# Temp_Project.net
KiCad netlist of a schematic drawn in EAGLE
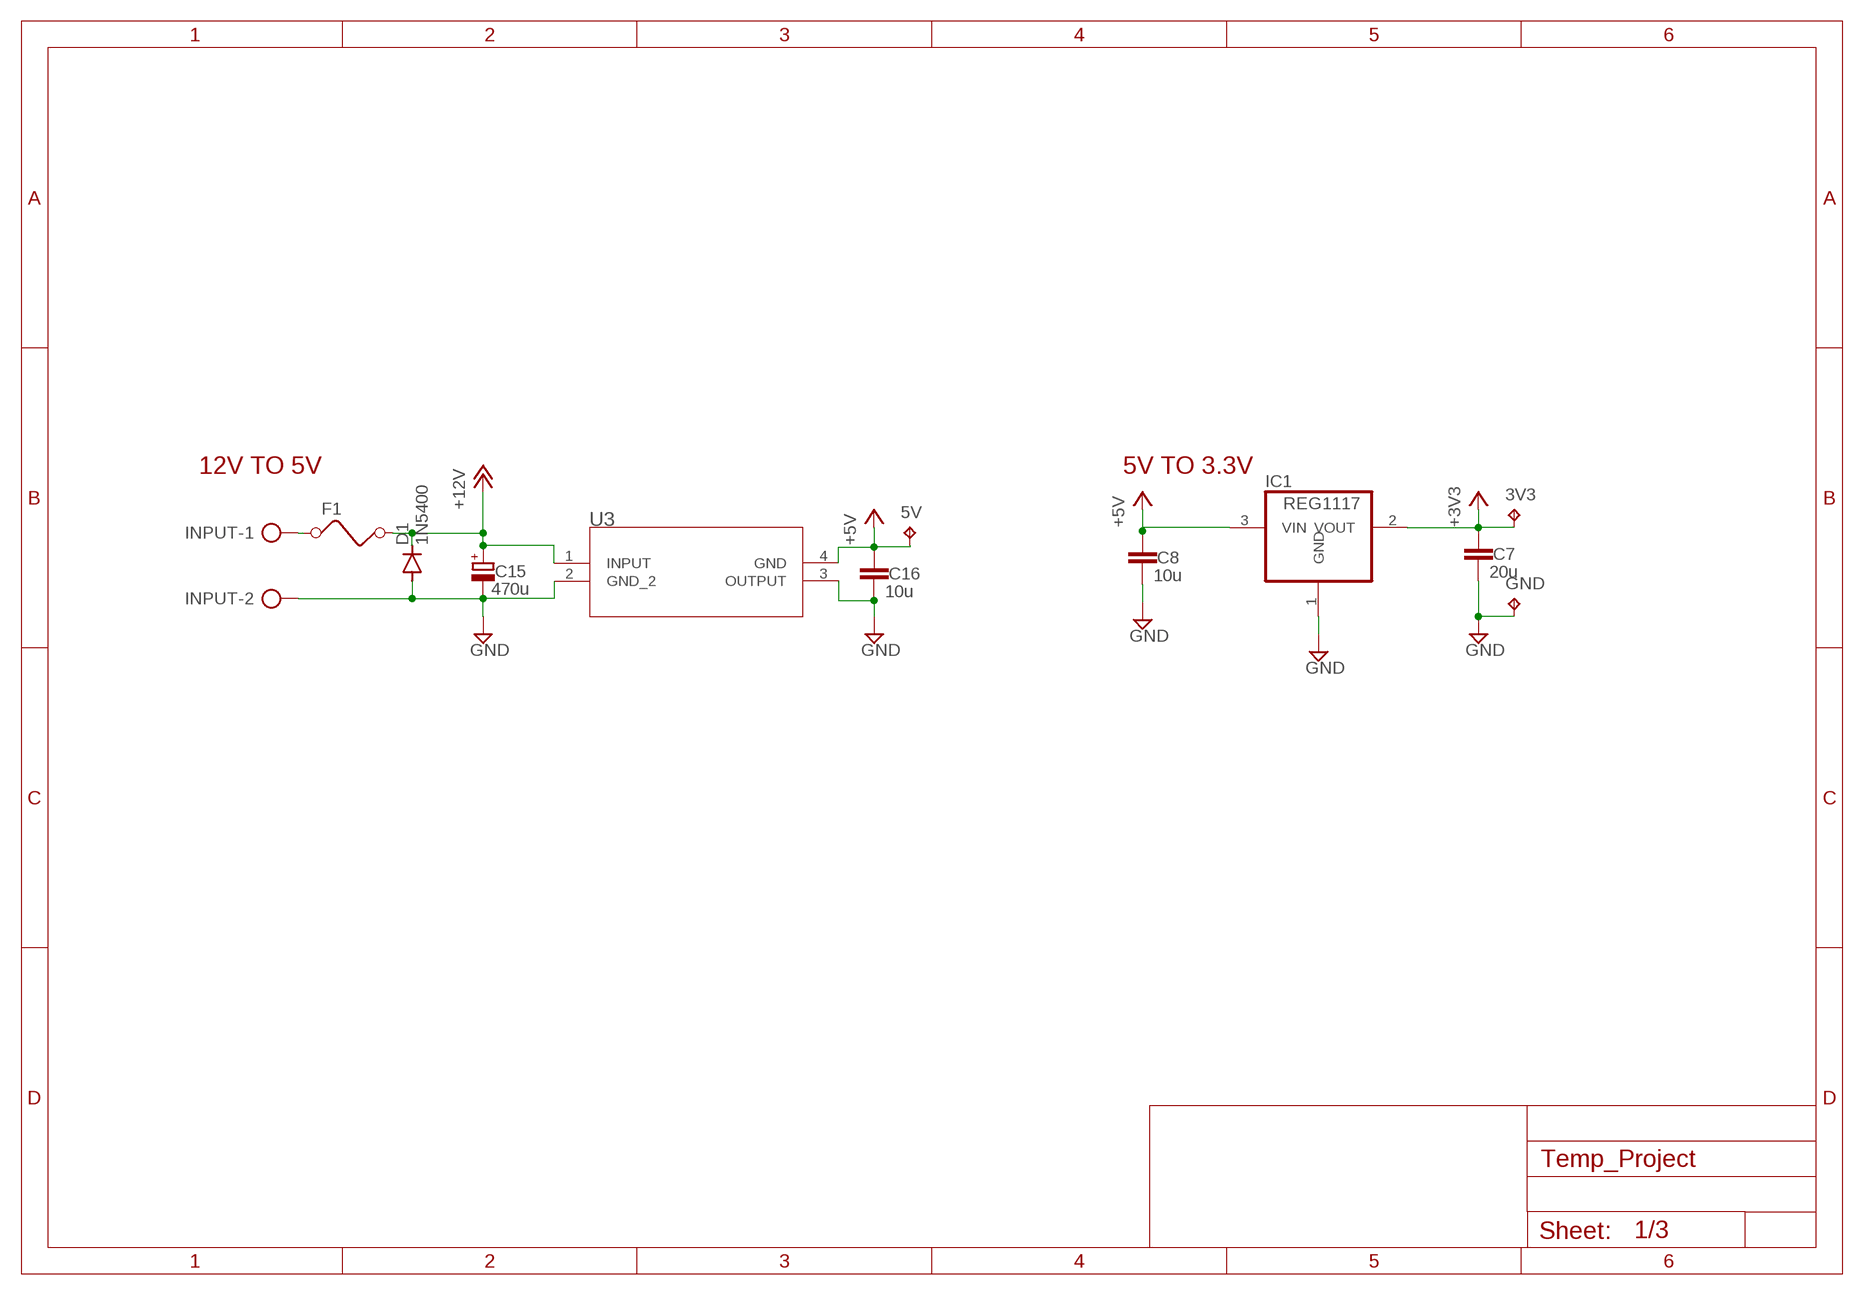
[diagram p0: schematic, sheet 1]
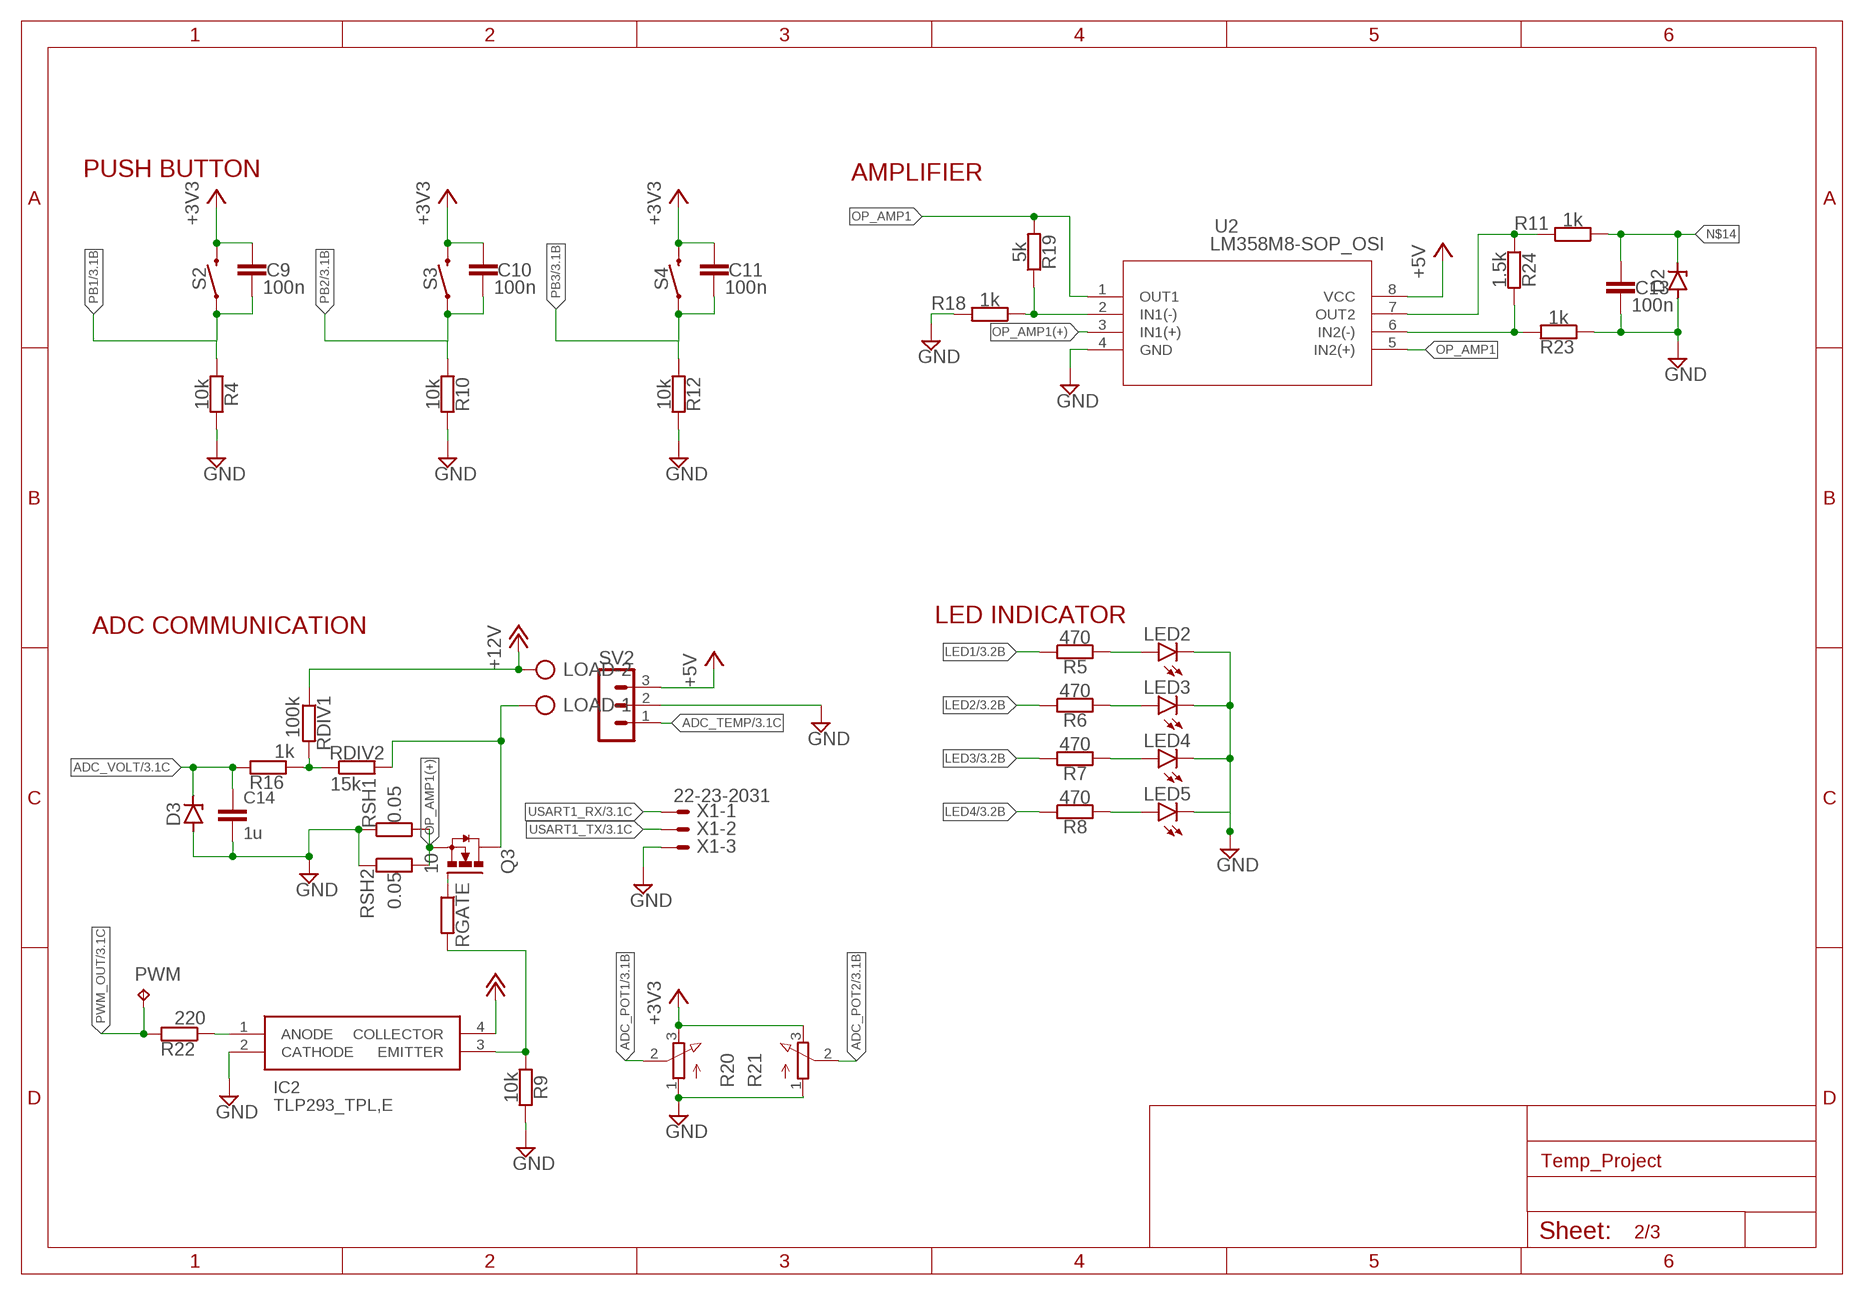
[diagram p1: schematic, sheet 2]
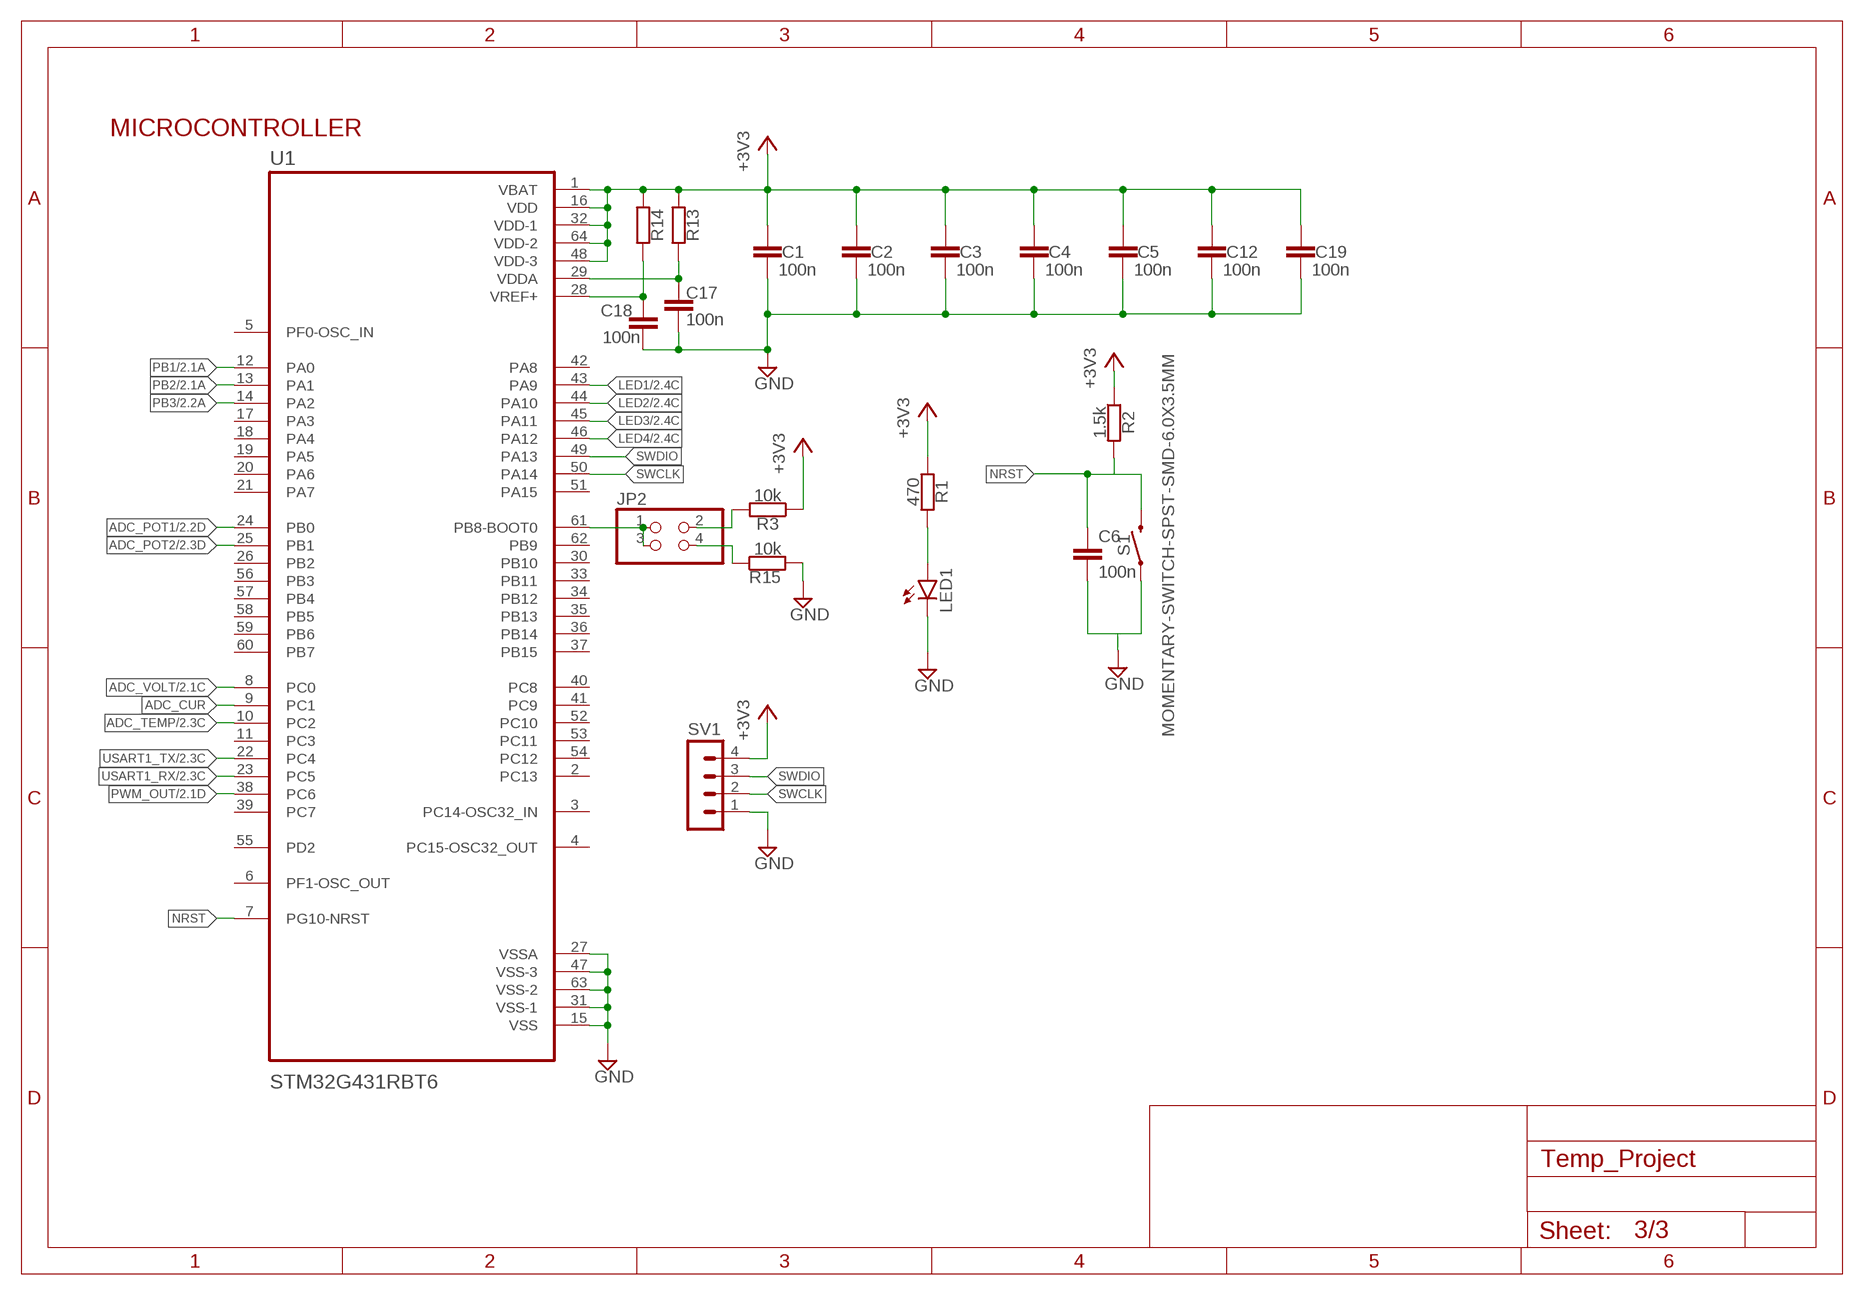
[diagram p2: schematic, sheet 3]

(export (version "E")
  (design (tool "Eeschema 10.0.6"))
  (components
    (comp (ref "C9")
      (value "100n")
      (footprint "eagle-import:C0805")
      (libsource (lib "eagle-import") (part "C-EUC0805"))
    )
    (comp (ref "C10")
      (value "100n")
      (footprint "eagle-import:C0805")
      (libsource (lib "eagle-import") (part "C-EUC0805"))
    )
    (comp (ref "C11")
      (value "100n")
      (footprint "eagle-import:C0805")
      (libsource (lib "eagle-import") (part "C-EUC0805"))
    )
    (comp (ref "C13")
      (value "100n")
      (footprint "eagle-import:C0805")
      (libsource (lib "eagle-import") (part "C-EUC0805"))
    )
    (comp (ref "C14")
      (value "1u")
      (footprint "eagle-import:C0805")
      (libsource (lib "eagle-import") (part "C-EUC0805"))
    )
    (comp (ref "D2")
      (value "ZENER 3V3")
      (footprint "eagle-import:SOD80C")
      (libsource (lib "eagle-import") (part "ZENER-DIODESOD80C"))
    )
    (comp (ref "D3")
      (value "ZENER 3V3")
      (footprint "eagle-import:SOD80C")
      (libsource (lib "eagle-import") (part "ZENER-DIODESOD80C"))
    )
    (comp (ref "IC2")
      (value "TLP293_TPL,E")
      (footprint "eagle-import:SOIC127P700X220-4N")
      (fields
        (field (name "MANUFACTURER_PART_NUMBER") "TLP293(TPL,E")
        (field (name "MOUSER_PART_NUMBER") "757-TLP293TPLE")
      )
      (libsource (lib "eagle-import") (part "TLP293_TPL,E"))
    )
    (comp (ref "LED2")
      (value "LED3MM")
      (footprint "eagle-import:LED3MM")
      (libsource (lib "eagle-import") (part "LED3MM"))
    )
    (comp (ref "LED3")
      (value "LED3MM")
      (footprint "eagle-import:LED3MM")
      (libsource (lib "eagle-import") (part "LED3MM"))
    )
    (comp (ref "LED4")
      (value "LED3MM")
      (footprint "eagle-import:LED3MM")
      (libsource (lib "eagle-import") (part "LED3MM"))
    )
    (comp (ref "LED5")
      (value "LED3MM")
      (footprint "eagle-import:LED3MM")
      (libsource (lib "eagle-import") (part "LED3MM"))
    )
    (comp (ref "LOAD")
      (value "AK500/2-H")
      (footprint "eagle-import:AK500_2-H")
      (libsource (lib "eagle-import") (part "con-ptr500_44290620_AK500/2-H"))
    )
    (comp (ref "PWM")
      (value "TPPAD1-13")
      (footprint "eagle-import:P1-13")
      (libsource (lib "eagle-import") (part "TPPAD1-13"))
    )
    (comp (ref "Q3")
      (value "IRFZ44N")
      (footprint "eagle-import:SOT223")
      (libsource (lib "eagle-import") (part "N-HEXFET-2D_?-SOT232"))
    )
    (comp (ref "R4")
      (value "10k")
      (footprint "eagle-import:R0805")
      (libsource (lib "eagle-import") (part "R-EU_R0805"))
    )
    (comp (ref "R5")
      (value "470")
      (footprint "eagle-import:R0805")
      (libsource (lib "eagle-import") (part "R-EU_R0805"))
    )
    (comp (ref "R6")
      (value "470")
      (footprint "eagle-import:R0805")
      (libsource (lib "eagle-import") (part "R-EU_R0805"))
    )
    (comp (ref "R7")
      (value "470")
      (footprint "eagle-import:R0805")
      (libsource (lib "eagle-import") (part "R-EU_R0805"))
    )
    (comp (ref "R8")
      (value "470")
      (footprint "eagle-import:R0805")
      (libsource (lib "eagle-import") (part "R-EU_R0805"))
    )
    (comp (ref "R9")
      (value "10k")
      (footprint "eagle-import:R0805")
      (libsource (lib "eagle-import") (part "R-EU_R0805"))
    )
    (comp (ref "R10")
      (value "10k")
      (footprint "eagle-import:R0805")
      (libsource (lib "eagle-import") (part "R-EU_R0805"))
    )
    (comp (ref "R11")
      (value "1k")
      (footprint "eagle-import:R0805")
      (libsource (lib "eagle-import") (part "R-EU_R0805"))
    )
    (comp (ref "R12")
      (value "10k")
      (footprint "eagle-import:R0805")
      (libsource (lib "eagle-import") (part "R-EU_R0805"))
    )
    (comp (ref "R16")
      (value "1k")
      (footprint "eagle-import:R0805")
      (libsource (lib "eagle-import") (part "R-EU_R0805"))
    )
    (comp (ref "R18")
      (value "1k")
      (footprint "eagle-import:R0805")
      (libsource (lib "eagle-import") (part "R-EU_R0805"))
    )
    (comp (ref "R19")
      (value "5k")
      (footprint "eagle-import:R0805")
      (libsource (lib "eagle-import") (part "R-EU_R0805"))
    )
    (comp (ref "R20")
      (value "3RP/1610N")
      (footprint "eagle-import:3RP_1610N")
      (libsource (lib "eagle-import") (part "3RP/1610N"))
    )
    (comp (ref "R21")
      (value "3RP/1610N")
      (footprint "eagle-import:3RP_1610N")
      (libsource (lib "eagle-import") (part "3RP/1610N"))
    )
    (comp (ref "R22")
      (value "220")
      (footprint "eagle-import:R0805")
      (libsource (lib "eagle-import") (part "R-EU_R0805"))
    )
    (comp (ref "R23")
      (value "1k")
      (footprint "eagle-import:R0805")
      (libsource (lib "eagle-import") (part "R-EU_R0805"))
    )
    (comp (ref "R24")
      (value "1.5k")
      (footprint "eagle-import:R0805")
      (libsource (lib "eagle-import") (part "R-EU_R0805"))
    )
    (comp (ref "RDIV1")
      (value "100k")
      (footprint "eagle-import:R0805")
      (libsource (lib "eagle-import") (part "R-EU_R0805"))
    )
    (comp (ref "RDIV2")
      (value "15k")
      (footprint "eagle-import:R0805")
      (libsource (lib "eagle-import") (part "R-EU_R0805"))
    )
    (comp (ref "RGATE")
      (value "10")
      (footprint "eagle-import:R0805")
      (libsource (lib "eagle-import") (part "R-EU_R0805"))
    )
    (comp (ref "RSH1")
      (value "0.05")
      (footprint "eagle-import:0617_22")
      (libsource (lib "eagle-import") (part "R-EU_0617/22"))
    )
    (comp (ref "RSH2")
      (value "0.05")
      (footprint "eagle-import:0617_22")
      (libsource (lib "eagle-import") (part "R-EU_0617/22"))
    )
    (comp (ref "S2")
      (value "MOMENTARY-SWITCH-SPST-SMD-6.0X3.5MM")
      (footprint "eagle-import:TACTILE_SWITCH_SMD_6.0X3.5MM")
      (libsource (lib "eagle-import") (part "MOMENTARY-SWITCH-SPST-SMD-6.0X3.5MM"))
    )
    (comp (ref "S3")
      (value "MOMENTARY-SWITCH-SPST-SMD-6.0X3.5MM")
      (footprint "eagle-import:TACTILE_SWITCH_SMD_6.0X3.5MM")
      (libsource (lib "eagle-import") (part "MOMENTARY-SWITCH-SPST-SMD-6.0X3.5MM"))
    )
    (comp (ref "S4")
      (value "MOMENTARY-SWITCH-SPST-SMD-6.0X3.5MM")
      (footprint "eagle-import:TACTILE_SWITCH_SMD_6.0X3.5MM")
      (libsource (lib "eagle-import") (part "MOMENTARY-SWITCH-SPST-SMD-6.0X3.5MM"))
    )
    (comp (ref "SV2")
      (value "MA03-1")
      (footprint "eagle-import:MA03-1")
      (libsource (lib "eagle-import") (part "MA03-1"))
    )
    (comp (ref "U2")
      (value "LM358M8-SOP_OSI")
      (footprint "eagle-import:8-SOP_OSI")
      (fields
        (field (name "MANUFACTURER_PART_NUMBER") "LM358M")
        (field (name "COPYRIGHT") "Copyright (C) 2024 Ultra Librarian. All rights reserved.")
      )
      (libsource (lib "eagle-import") (part "LM358M8-SOP_OSI"))
    )
    (comp (ref "X1")
      (value "22-23-2031")
      (footprint "eagle-import:22-23-2031")
      (fields (field (name "MF") "MOLEX"))
      (libsource (lib "eagle-import") (part "22-23-2031"))
    )
    (comp (ref "C1")
      (value "100n")
      (footprint "eagle-import:C0805")
      (libsource (lib "eagle-import") (part "C-EUC0805"))
    )
    (comp (ref "C2")
      (value "100n")
      (footprint "eagle-import:C0805")
      (libsource (lib "eagle-import") (part "C-EUC0805"))
    )
    (comp (ref "C3")
      (value "100n")
      (footprint "eagle-import:C0805")
      (libsource (lib "eagle-import") (part "C-EUC0805"))
    )
    (comp (ref "C4")
      (value "100n")
      (footprint "eagle-import:C0805")
      (libsource (lib "eagle-import") (part "C-EUC0805"))
    )
    (comp (ref "C5")
      (value "100n")
      (footprint "eagle-import:C0805")
      (libsource (lib "eagle-import") (part "C-EUC0805"))
    )
    (comp (ref "C6")
      (value "100n")
      (footprint "eagle-import:C0805")
      (libsource (lib "eagle-import") (part "C-EUC0805"))
    )
    (comp (ref "C12")
      (value "100n")
      (footprint "eagle-import:C0805")
      (libsource (lib "eagle-import") (part "C-EUC0805"))
    )
    (comp (ref "C17")
      (value "100n")
      (footprint "eagle-import:C0805")
      (libsource (lib "eagle-import") (part "C-EUC0805"))
    )
    (comp (ref "C18")
      (value "100n")
      (footprint "eagle-import:C0805")
      (libsource (lib "eagle-import") (part "C-EUC0805"))
    )
    (comp (ref "C19")
      (value "100n")
      (footprint "eagle-import:C0805")
      (libsource (lib "eagle-import") (part "C-EUC0805"))
    )
    (comp (ref "JP2")
      (value "PINHD-2X2")
      (footprint "eagle-import:2X02")
      (libsource (lib "eagle-import") (part "PINHD-2X2"))
    )
    (comp (ref "LED1")
      (value "LEDCHIPLED_0805")
      (footprint "eagle-import:CHIPLED_0805")
      (libsource (lib "eagle-import") (part "LEDCHIPLED_0805"))
    )
    (comp (ref "R1")
      (value "470")
      (footprint "eagle-import:R0805")
      (libsource (lib "eagle-import") (part "R-EU_R0805"))
    )
    (comp (ref "R2")
      (value "1.5k")
      (footprint "eagle-import:R0805")
      (libsource (lib "eagle-import") (part "R-EU_R0805"))
    )
    (comp (ref "R3")
      (value "10k")
      (footprint "eagle-import:R0805")
      (libsource (lib "eagle-import") (part "R-EU_R0805"))
    )
    (comp (ref "R13")
      (value "R-EU_R0603")
      (footprint "eagle-import:R0603")
      (libsource (lib "eagle-import") (part "R-EU_R0603"))
    )
    (comp (ref "R14")
      (value "R-EU_R0603")
      (footprint "eagle-import:R0603")
      (libsource (lib "eagle-import") (part "R-EU_R0603"))
    )
    (comp (ref "R15")
      (value "10k")
      (footprint "eagle-import:R0805")
      (libsource (lib "eagle-import") (part "R-EU_R0805"))
    )
    (comp (ref "S1")
      (value "MOMENTARY-SWITCH-SPST-SMD-6.0X3.5MM")
      (footprint "eagle-import:TACTILE_SWITCH_SMD_6.0X3.5MM")
      (libsource (lib "eagle-import") (part "MOMENTARY-SWITCH-SPST-SMD-6.0X3.5MM"))
    )
    (comp (ref "SV1")
      (value "MA04-1")
      (footprint "eagle-import:MA04-1")
      (libsource (lib "eagle-import") (part "MA04-1"))
    )
    (comp (ref "U1")
      (value "STM32G431RBT6")
      (footprint "eagle-import:QFP50P1200X1200X160-64N")
      (fields (field (name "MANUFACTURER") "STMicroelectronics"))
      (libsource (lib "eagle-import") (part "STM32G431RBT6"))
    )
    (comp (ref "3V3")
      (value "TPPAD1-13")
      (footprint "eagle-import:P1-13")
      (libsource (lib "eagle-import") (part "TPPAD1-13"))
    )
    (comp (ref "5V")
      (value "TPPAD1-13")
      (footprint "eagle-import:P1-13")
      (libsource (lib "eagle-import") (part "TPPAD1-13"))
    )
    (comp (ref "C7")
      (value "20u")
      (footprint "eagle-import:C0805")
      (libsource (lib "eagle-import") (part "C-EUC0805"))
    )
    (comp (ref "C8")
      (value "10u")
      (footprint "eagle-import:C0805")
      (libsource (lib "eagle-import") (part "C-EUC0805"))
    )
    (comp (ref "C15")
      (value "470u")
      (footprint "eagle-import:E5-10,5")
      (libsource (lib "eagle-import") (part "CPOL-EUE5-10.5"))
    )
    (comp (ref "C16")
      (value "10u")
      (footprint "eagle-import:C0805")
      (libsource (lib "eagle-import") (part "C-EUC0805"))
    )
    (comp (ref "D1")
      (value "1N5400")
      (footprint "eagle-import:DO201-15")
      (libsource (lib "eagle-import") (part "1N5400"))
    )
    (comp (ref "F1")
      (value "FUSE")
      (footprint "eagle-import:FUSE")
      (libsource (lib "eagle-import") (part "FUSE"))
    )
    (comp (ref "GND")
      (value "TPPAD1-13")
      (footprint "eagle-import:P1-13")
      (libsource (lib "eagle-import") (part "TPPAD1-13"))
    )
    (comp (ref "IC1")
      (value "REG1117")
      (footprint "eagle-import:SOT223")
      (libsource (lib "eagle-import") (part "REG1117"))
    )
    (comp (ref "INPUT")
      (value "AK500/2-H")
      (footprint "eagle-import:AK500_2-H")
      (libsource (lib "eagle-import") (part "AK500/2-H"))
    )
    (comp (ref "U3")
      (value "LM7805MPX/NOPBDCY4_TEX")
      (footprint "eagle-import:DCY4_TEX")
      (fields
        (field (name "MANUFACTURER_PART_NUMBER") "LM7805MPX/NOPB")
        (field (name "COPYRIGHT") "Copyright (C) 2024 Ultra Librarian. All rights reserved.")
      )
      (libsource (lib "eagle-import") (part "LM7805MPX/NOPBDCY4_TEX"))
    )
  )
  (nets
    (net (code "1") (name "+3V3") (class "Default")
      (node (ref "3V3") (pin "TP") (pinfunction "TP_TP") (pintype "input"))
      (node (ref "C1") (pin "1") (pinfunction "1_1") (pintype "passive"))
      (node (ref "C10") (pin "1") (pinfunction "1_1") (pintype "passive"))
      (node (ref "C11") (pin "1") (pinfunction "1_1") (pintype "passive"))
      (node (ref "C12") (pin "1") (pinfunction "1_1") (pintype "passive"))
      (node (ref "C19") (pin "1") (pinfunction "1_1") (pintype "passive"))
      (node (ref "C2") (pin "1") (pinfunction "1_1") (pintype "passive"))
      (node (ref "C3") (pin "1") (pinfunction "1_1") (pintype "passive"))
      (node (ref "C4") (pin "1") (pinfunction "1_1") (pintype "passive"))
      (node (ref "C5") (pin "1") (pinfunction "1_1") (pintype "passive"))
      (node (ref "C7") (pin "1") (pinfunction "1_1") (pintype "passive"))
      (node (ref "C9") (pin "1") (pinfunction "1_1") (pintype "passive"))
      (node (ref "IC1") (pin "2") (pinfunction "VOUT_2") (pintype "output"))
      (node (ref "R1") (pin "1") (pinfunction "1_1") (pintype "passive"))
      (node (ref "R13") (pin "2") (pinfunction "2_2") (pintype "passive"))
      (node (ref "R14") (pin "2") (pinfunction "2_2") (pintype "passive"))
      (node (ref "R2") (pin "1") (pinfunction "1_1") (pintype "passive"))
      (node (ref "R20") (pin "3") (pinfunction "E_3") (pintype "passive"))
      (node (ref "R21") (pin "3") (pinfunction "E_3") (pintype "passive"))
      (node (ref "R3") (pin "1") (pinfunction "1_1") (pintype "passive"))
      (node (ref "S2") (pin "2") (pinfunction "2_2") (pintype "passive"))
      (node (ref "S3") (pin "2") (pinfunction "2_2") (pintype "passive"))
      (node (ref "S4") (pin "2") (pinfunction "2_2") (pintype "passive"))
      (node (ref "SV1") (pin "4") (pinfunction "4_4") (pintype "passive"))
      (node (ref "U1") (pin "1") (pinfunction "VBAT_1") (pintype "power_in"))
      (node (ref "U1") (pin "16") (pinfunction "VDD_16") (pintype "power_in"))
      (node (ref "U1") (pin "32") (pinfunction "VDD-1_32") (pintype "power_in"))
      (node (ref "U1") (pin "48") (pinfunction "VDD-3_48") (pintype "power_in"))
      (node (ref "U1") (pin "64") (pinfunction "VDD-2_64") (pintype "power_in"))
    )
    (net (code "2") (name "+5V") (class "Default")
      (node (ref "5V") (pin "TP") (pinfunction "TP_TP") (pintype "input"))
      (node (ref "C16") (pin "1") (pinfunction "1_1") (pintype "passive"))
      (node (ref "C8") (pin "1") (pinfunction "1_1") (pintype "passive"))
      (node (ref "IC1") (pin "3") (pinfunction "VIN_3") (pintype "input"))
      (node (ref "SV2") (pin "3") (pinfunction "3_3") (pintype "passive"))
      (node (ref "U2") (pin "8") (pinfunction "VCC_8") (pintype "power_in"))
      (node (ref "U3") (pin "4") (pinfunction "GND_4") (pintype "power_in"))
    )
    (net (code "3") (name "+12V") (class "Default")
      (node (ref "C15") (pin "+") (pinfunction "+_+") (pintype "passive"))
      (node (ref "D1") (pin "C") (pinfunction "C_C") (pintype "passive"))
      (node (ref "F1") (pin "2") (pinfunction "2_2") (pintype "passive"))
      (node (ref "IC2") (pin "4") (pinfunction "COLLECTOR_4") (pintype "bidirectional"))
      (node (ref "LOAD") (pin "2") (pinfunction "KL_2") (pintype "passive"))
      (node (ref "RDIV1") (pin "1") (pinfunction "1_1") (pintype "passive"))
      (node (ref "U3") (pin "1") (pinfunction "INPUT_1") (pintype "input"))
    )
    (net (code "4") (name "ADC_CUR") (class "Default")
      (node (ref "R11") (pin "2") (pinfunction "2_2") (pintype "passive"))
      (node (ref "R24") (pin "1") (pinfunction "1_1") (pintype "passive"))
      (node (ref "U1") (pin "9") (pinfunction "PC1_9") (pintype "bidirectional"))
      (node (ref "U2") (pin "7") (pinfunction "OUT2_7") (pintype "output"))
    )
    (net (code "5") (name "ADC_POT1") (class "Default")
      (node (ref "R20") (pin "2") (pinfunction "S_2") (pintype "passive"))
      (node (ref "U1") (pin "24") (pinfunction "PB0_24") (pintype "bidirectional"))
    )
    (net (code "6") (name "ADC_POT2") (class "Default")
      (node (ref "R21") (pin "2") (pinfunction "S_2") (pintype "passive"))
      (node (ref "U1") (pin "25") (pinfunction "PB1_25") (pintype "bidirectional"))
    )
    (net (code "7") (name "ADC_TEMP") (class "Default")
      (node (ref "SV2") (pin "1") (pinfunction "1_1") (pintype "passive"))
      (node (ref "U1") (pin "10") (pinfunction "PC2_10") (pintype "bidirectional"))
    )
    (net (code "8") (name "ADC_VOLT") (class "Default")
      (node (ref "C14") (pin "1") (pinfunction "1_1") (pintype "passive"))
      (node (ref "D3") (pin "C") (pinfunction "C_C") (pintype "passive"))
      (node (ref "R16") (pin "2") (pinfunction "2_2") (pintype "passive"))
      (node (ref "U1") (pin "8") (pinfunction "PC0_8") (pintype "bidirectional"))
    )
    (net (code "9") (name "GND") (class "Default")
      (node (ref "C1") (pin "2") (pinfunction "2_2") (pintype "passive"))
      (node (ref "C12") (pin "2") (pinfunction "2_2") (pintype "passive"))
      (node (ref "C13") (pin "2") (pinfunction "2_2") (pintype "passive"))
      (node (ref "C14") (pin "2") (pinfunction "2_2") (pintype "passive"))
      (node (ref "C15") (pin "-") (pinfunction "-_-") (pintype "passive"))
      (node (ref "C16") (pin "2") (pinfunction "2_2") (pintype "passive"))
      (node (ref "C17") (pin "2") (pinfunction "2_2") (pintype "passive"))
      (node (ref "C18") (pin "2") (pinfunction "2_2") (pintype "passive"))
      (node (ref "C19") (pin "2") (pinfunction "2_2") (pintype "passive"))
      (node (ref "C2") (pin "2") (pinfunction "2_2") (pintype "passive"))
      (node (ref "C3") (pin "2") (pinfunction "2_2") (pintype "passive"))
      (node (ref "C4") (pin "2") (pinfunction "2_2") (pintype "passive"))
      (node (ref "C5") (pin "2") (pinfunction "2_2") (pintype "passive"))
      (node (ref "C6") (pin "2") (pinfunction "2_2") (pintype "passive"))
      (node (ref "C7") (pin "2") (pinfunction "2_2") (pintype "passive"))
      (node (ref "C8") (pin "2") (pinfunction "2_2") (pintype "passive"))
      (node (ref "D1") (pin "A") (pinfunction "A_A") (pintype "passive"))
      (node (ref "D2") (pin "A") (pinfunction "A_A") (pintype "passive"))
      (node (ref "D3") (pin "A") (pinfunction "A_A") (pintype "passive"))
      (node (ref "GND") (pin "TP") (pinfunction "TP_TP") (pintype "input"))
      (node (ref "IC1") (pin "1") (pinfunction "GND_1") (pintype "power_in"))
      (node (ref "IC2") (pin "2") (pinfunction "CATHODE_2") (pintype "bidirectional"))
      (node (ref "INPUT") (pin "2") (pinfunction "KL_2") (pintype "passive"))
      (node (ref "LED1") (pin "C") (pinfunction "C_C") (pintype "passive"))
      (node (ref "LED2") (pin "K") (pinfunction "C_K") (pintype "passive"))
      (node (ref "LED3") (pin "K") (pinfunction "C_K") (pintype "passive"))
      (node (ref "LED4") (pin "K") (pinfunction "C_K") (pintype "passive"))
      (node (ref "LED5") (pin "K") (pinfunction "C_K") (pintype "passive"))
      (node (ref "R10") (pin "1") (pinfunction "1_1") (pintype "passive"))
      (node (ref "R12") (pin "1") (pinfunction "1_1") (pintype "passive"))
      (node (ref "R15") (pin "2") (pinfunction "2_2") (pintype "passive"))
      (node (ref "R18") (pin "2") (pinfunction "2_2") (pintype "passive"))
      (node (ref "R20") (pin "1") (pinfunction "A_1") (pintype "passive"))
      (node (ref "R21") (pin "1") (pinfunction "A_1") (pintype "passive"))
      (node (ref "R23") (pin "1") (pinfunction "1_1") (pintype "passive"))
      (node (ref "R4") (pin "1") (pinfunction "1_1") (pintype "passive"))
      (node (ref "R9") (pin "1") (pinfunction "1_1") (pintype "passive"))
      (node (ref "RSH1") (pin "1") (pinfunction "1_1") (pintype "passive"))
      (node (ref "RSH2") (pin "1") (pinfunction "1_1") (pintype "passive"))
      (node (ref "S1") (pin "1") (pinfunction "1_1") (pintype "passive"))
      (node (ref "SV1") (pin "1") (pinfunction "1_1") (pintype "passive"))
      (node (ref "SV2") (pin "2") (pinfunction "2_2") (pintype "passive"))
      (node (ref "U1") (pin "15") (pinfunction "VSS_15") (pintype "power_in"))
      (node (ref "U1") (pin "27") (pinfunction "VSSA_27") (pintype "power_in"))
      (node (ref "U1") (pin "31") (pinfunction "VSS-1_31") (pintype "power_in"))
      (node (ref "U1") (pin "47") (pinfunction "VSS-3_47") (pintype "power_in"))
      (node (ref "U1") (pin "63") (pinfunction "VSS-2_63") (pintype "power_in"))
      (node (ref "U2") (pin "4") (pinfunction "GND_4") (pintype "passive"))
      (node (ref "U3") (pin "2") (pinfunction "GND_2_2") (pintype "power_in"))
      (node (ref "U3") (pin "3") (pinfunction "OUTPUT_3") (pintype "output"))
      (node (ref "X1") (pin "3") (pinfunction "S_3") (pintype "passive"))
    )
    (net (code "10") (name "LED1") (class "Default")
      (node (ref "R5") (pin "1") (pinfunction "1_1") (pintype "passive"))
      (node (ref "U1") (pin "43") (pinfunction "PA9_43") (pintype "bidirectional"))
    )
    (net (code "11") (name "LED2") (class "Default")
      (node (ref "R6") (pin "1") (pinfunction "1_1") (pintype "passive"))
      (node (ref "U1") (pin "44") (pinfunction "PA10_44") (pintype "bidirectional"))
    )
    (net (code "12") (name "LED3") (class "Default")
      (node (ref "R7") (pin "1") (pinfunction "1_1") (pintype "passive"))
      (node (ref "U1") (pin "45") (pinfunction "PA11_45") (pintype "bidirectional"))
    )
    (net (code "13") (name "LED4") (class "Default")
      (node (ref "R8") (pin "1") (pinfunction "1_1") (pintype "passive"))
      (node (ref "U1") (pin "46") (pinfunction "PA12_46") (pintype "bidirectional"))
    )
    (net (code "14") (name "N$14") (class "Default")
      (node (ref "C13") (pin "1") (pinfunction "1_1") (pintype "passive"))
      (node (ref "D2") (pin "C") (pinfunction "C_C") (pintype "passive"))
      (node (ref "R11") (pin "1") (pinfunction "1_1") (pintype "passive"))
    )
    (net (code "15") (name "NRST") (class "Default")
      (node (ref "C6") (pin "1") (pinfunction "1_1") (pintype "passive"))
      (node (ref "R2") (pin "2") (pinfunction "2_2") (pintype "passive"))
      (node (ref "S1") (pin "2") (pinfunction "2_2") (pintype "passive"))
      (node (ref "U1") (pin "7") (pinfunction "PG10-NRST_7") (pintype "bidirectional"))
    )
    (net (code "16") (name "Net-(IC2-ANODE)") (class "Default")
      (node (ref "IC2") (pin "1") (pinfunction "ANODE_1") (pintype "bidirectional"))
      (node (ref "R22") (pin "1") (pinfunction "1_1") (pintype "passive"))
    )
    (net (code "17") (name "Net-(IC2-EMITTER)") (class "Default")
      (node (ref "IC2") (pin "3") (pinfunction "EMITTER_3") (pintype "bidirectional"))
      (node (ref "R9") (pin "2") (pinfunction "2_2") (pintype "passive"))
      (node (ref "RGATE") (pin "2") (pinfunction "2_2") (pintype "passive"))
    )
    (net (code "18") (name "Net-(INPUTA-KL)") (class "Default")
      (node (ref "F1") (pin "1") (pinfunction "1_1") (pintype "passive"))
      (node (ref "INPUT") (pin "1") (pinfunction "KL_1") (pintype "passive"))
    )
    (net (code "19") (name "Net-(JP2-Pad2)") (class "Default")
      (node (ref "JP2") (pin "2") (pinfunction "2_2") (pintype "passive"))
      (node (ref "R3") (pin "2") (pinfunction "2_2") (pintype "passive"))
    )
    (net (code "20") (name "Net-(JP2-Pad4)") (class "Default")
      (node (ref "JP2") (pin "4") (pinfunction "4_4") (pintype "passive"))
      (node (ref "R15") (pin "1") (pinfunction "1_1") (pintype "passive"))
    )
    (net (code "21") (name "Net-(LED1-PadA)") (class "Default")
      (node (ref "LED1") (pin "A") (pinfunction "A_A") (pintype "passive"))
      (node (ref "R1") (pin "2") (pinfunction "2_2") (pintype "passive"))
    )
    (net (code "22") (name "Net-(LED2-PadA)") (class "Default")
      (node (ref "LED2") (pin "A") (pinfunction "A_A") (pintype "passive"))
      (node (ref "R5") (pin "2") (pinfunction "2_2") (pintype "passive"))
    )
    (net (code "23") (name "Net-(LED3-PadA)") (class "Default")
      (node (ref "LED3") (pin "A") (pinfunction "A_A") (pintype "passive"))
      (node (ref "R6") (pin "2") (pinfunction "2_2") (pintype "passive"))
    )
    (net (code "24") (name "Net-(LED4-PadA)") (class "Default")
      (node (ref "LED4") (pin "A") (pinfunction "A_A") (pintype "passive"))
      (node (ref "R7") (pin "2") (pinfunction "2_2") (pintype "passive"))
    )
    (net (code "25") (name "Net-(LED5-PadA)") (class "Default")
      (node (ref "LED5") (pin "A") (pinfunction "A_A") (pintype "passive"))
      (node (ref "R8") (pin "2") (pinfunction "2_2") (pintype "passive"))
    )
    (net (code "26") (name "Net-(LOADA-KL)") (class "Default")
      (node (ref "LOAD") (pin "1") (pinfunction "KL_1") (pintype "passive"))
      (node (ref "Q3") (pin "2") (pinfunction "D_2") (pintype "passive"))
      (node (ref "Q3") (pin "4") (pinfunction "D_4") (pintype "passive"))
      (node (ref "RDIV2") (pin "2") (pinfunction "2_2") (pintype "passive"))
    )
    (net (code "27") (name "Net-(Q3-G)") (class "Default")
      (node (ref "Q3") (pin "1") (pinfunction "G_1") (pintype "passive"))
      (node (ref "RGATE") (pin "1") (pinfunction "1_1") (pintype "passive"))
    )
    (net (code "28") (name "Net-(R16-Pad1)") (class "Default")
      (node (ref "R16") (pin "1") (pinfunction "1_1") (pintype "passive"))
      (node (ref "RDIV1") (pin "2") (pinfunction "2_2") (pintype "passive"))
      (node (ref "RDIV2") (pin "1") (pinfunction "1_1") (pintype "passive"))
    )
    (net (code "29") (name "Net-(U1-PB8-BOOT0)") (class "Default")
      (node (ref "JP2") (pin "1") (pinfunction "1_1") (pintype "passive"))
      (node (ref "JP2") (pin "3") (pinfunction "3_3") (pintype "passive"))
      (node (ref "U1") (pin "61") (pinfunction "PB8-BOOT0_61") (pintype "bidirectional"))
    )
    (net (code "30") (name "Net-(U1-VDDA)") (class "Default")
      (node (ref "C17") (pin "1") (pinfunction "1_1") (pintype "passive"))
      (node (ref "R13") (pin "1") (pinfunction "1_1") (pintype "passive"))
      (node (ref "U1") (pin "29") (pinfunction "VDDA_29") (pintype "power_in"))
    )
    (net (code "31") (name "Net-(U1-VREF+)") (class "Default")
      (node (ref "C18") (pin "1") (pinfunction "1_1") (pintype "passive"))
      (node (ref "R14") (pin "1") (pinfunction "1_1") (pintype "passive"))
      (node (ref "U1") (pin "28") (pinfunction "VREF+_28") (pintype "power_in"))
    )
    (net (code "32") (name "Net-(U2-IN1(-))") (class "Default")
      (node (ref "R18") (pin "1") (pinfunction "1_1") (pintype "passive"))
      (node (ref "R19") (pin "1") (pinfunction "1_1") (pintype "passive"))
      (node (ref "U2") (pin "2") (pinfunction "IN1(-)_2") (pintype "input"))
    )
    (net (code "33") (name "Net-(U2-IN2(-))") (class "Default")
      (node (ref "R23") (pin "2") (pinfunction "2_2") (pintype "passive"))
      (node (ref "R24") (pin "2") (pinfunction "2_2") (pintype "passive"))
      (node (ref "U2") (pin "6") (pinfunction "IN2(-)_6") (pintype "input"))
    )
    (net (code "34") (name "OP_AMP1") (class "Default")
      (node (ref "R19") (pin "2") (pinfunction "2_2") (pintype "passive"))
      (node (ref "U2") (pin "1") (pinfunction "OUT1_1") (pintype "output"))
      (node (ref "U2") (pin "5") (pinfunction "IN2(+)_5") (pintype "input"))
    )
    (net (code "35") (name "OP_AMP1(+)") (class "Default")
      (node (ref "Q3") (pin "3") (pinfunction "S_3") (pintype "passive"))
      (node (ref "RSH1") (pin "2") (pinfunction "2_2") (pintype "passive"))
      (node (ref "RSH2") (pin "2") (pinfunction "2_2") (pintype "passive"))
      (node (ref "U2") (pin "3") (pinfunction "IN1(+)_3") (pintype "input"))
    )
    (net (code "36") (name "PB1") (class "Default")
      (node (ref "C9") (pin "2") (pinfunction "2_2") (pintype "passive"))
      (node (ref "R4") (pin "2") (pinfunction "2_2") (pintype "passive"))
      (node (ref "S2") (pin "1") (pinfunction "1_1") (pintype "passive"))
      (node (ref "U1") (pin "12") (pinfunction "PA0_12") (pintype "bidirectional"))
    )
    (net (code "37") (name "PB2") (class "Default")
      (node (ref "C10") (pin "2") (pinfunction "2_2") (pintype "passive"))
      (node (ref "R10") (pin "2") (pinfunction "2_2") (pintype "passive"))
      (node (ref "S3") (pin "1") (pinfunction "1_1") (pintype "passive"))
      (node (ref "U1") (pin "13") (pinfunction "PA1_13") (pintype "bidirectional"))
    )
    (net (code "38") (name "PB3") (class "Default")
      (node (ref "C11") (pin "2") (pinfunction "2_2") (pintype "passive"))
      (node (ref "R12") (pin "2") (pinfunction "2_2") (pintype "passive"))
      (node (ref "S4") (pin "1") (pinfunction "1_1") (pintype "passive"))
      (node (ref "U1") (pin "14") (pinfunction "PA2_14") (pintype "bidirectional"))
    )
    (net (code "39") (name "PWM_OUT") (class "Default")
      (node (ref "PWM") (pin "TP") (pinfunction "TP_TP") (pintype "input"))
      (node (ref "R22") (pin "2") (pinfunction "2_2") (pintype "passive"))
      (node (ref "U1") (pin "38") (pinfunction "PC6_38") (pintype "bidirectional"))
    )
    (net (code "40") (name "SWCLK") (class "Default")
      (node (ref "SV1") (pin "2") (pinfunction "2_2") (pintype "passive"))
      (node (ref "U1") (pin "50") (pinfunction "PA14_50") (pintype "bidirectional"))
    )
    (net (code "41") (name "SWDIO") (class "Default")
      (node (ref "SV1") (pin "3") (pinfunction "3_3") (pintype "passive"))
      (node (ref "U1") (pin "49") (pinfunction "PA13_49") (pintype "bidirectional"))
    )
    (net (code "42") (name "USART1_RX") (class "Default")
      (node (ref "U1") (pin "23") (pinfunction "PC5_23") (pintype "bidirectional"))
      (node (ref "X1") (pin "1") (pinfunction "S_1") (pintype "passive"))
    )
    (net (code "43") (name "USART1_TX") (class "Default")
      (node (ref "U1") (pin "22") (pinfunction "PC4_22") (pintype "bidirectional"))
      (node (ref "X1") (pin "2") (pinfunction "S_2") (pintype "passive"))
    )
    (net (code "44") (name "unconnected-(U1-PA3-Pad17)") (class "Default")
      (node (ref "U1") (pin "17") (pinfunction "PA3_17") (pintype "bidirectional"))
    )
    (net (code "45") (name "unconnected-(U1-PA4-Pad18)") (class "Default")
      (node (ref "U1") (pin "18") (pinfunction "PA4_18") (pintype "bidirectional"))
    )
    (net (code "46") (name "unconnected-(U1-PA5-Pad19)") (class "Default")
      (node (ref "U1") (pin "19") (pinfunction "PA5_19") (pintype "bidirectional"))
    )
    (net (code "47") (name "unconnected-(U1-PA6-Pad20)") (class "Default")
      (node (ref "U1") (pin "20") (pinfunction "PA6_20") (pintype "bidirectional"))
    )
    (net (code "48") (name "unconnected-(U1-PA7-Pad21)") (class "Default")
      (node (ref "U1") (pin "21") (pinfunction "PA7_21") (pintype "bidirectional"))
    )
    (net (code "49") (name "unconnected-(U1-PA8-Pad42)") (class "Default")
      (node (ref "U1") (pin "42") (pinfunction "PA8_42") (pintype "bidirectional"))
    )
    (net (code "50") (name "unconnected-(U1-PA15-Pad51)") (class "Default")
      (node (ref "U1") (pin "51") (pinfunction "PA15_51") (pintype "bidirectional"))
    )
    (net (code "51") (name "unconnected-(U1-PB2-Pad26)") (class "Default")
      (node (ref "U1") (pin "26") (pinfunction "PB2_26") (pintype "bidirectional"))
    )
    (net (code "52") (name "unconnected-(U1-PB3-Pad56)") (class "Default")
      (node (ref "U1") (pin "56") (pinfunction "PB3_56") (pintype "bidirectional"))
    )
    (net (code "53") (name "unconnected-(U1-PB4-Pad57)") (class "Default")
      (node (ref "U1") (pin "57") (pinfunction "PB4_57") (pintype "bidirectional"))
    )
    (net (code "54") (name "unconnected-(U1-PB5-Pad58)") (class "Default")
      (node (ref "U1") (pin "58") (pinfunction "PB5_58") (pintype "bidirectional"))
    )
    (net (code "55") (name "unconnected-(U1-PB6-Pad59)") (class "Default")
      (node (ref "U1") (pin "59") (pinfunction "PB6_59") (pintype "bidirectional"))
    )
    (net (code "56") (name "unconnected-(U1-PB7-Pad60)") (class "Default")
      (node (ref "U1") (pin "60") (pinfunction "PB7_60") (pintype "bidirectional"))
    )
    (net (code "57") (name "unconnected-(U1-PB9-Pad62)") (class "Default")
      (node (ref "U1") (pin "62") (pinfunction "PB9_62") (pintype "bidirectional"))
    )
    (net (code "58") (name "unconnected-(U1-PB10-Pad30)") (class "Default")
      (node (ref "U1") (pin "30") (pinfunction "PB10_30") (pintype "bidirectional"))
    )
    (net (code "59") (name "unconnected-(U1-PB11-Pad33)") (class "Default")
      (node (ref "U1") (pin "33") (pinfunction "PB11_33") (pintype "bidirectional"))
    )
    (net (code "60") (name "unconnected-(U1-PB12-Pad34)") (class "Default")
      (node (ref "U1") (pin "34") (pinfunction "PB12_34") (pintype "bidirectional"))
    )
    (net (code "61") (name "unconnected-(U1-PB13-Pad35)") (class "Default")
      (node (ref "U1") (pin "35") (pinfunction "PB13_35") (pintype "bidirectional"))
    )
    (net (code "62") (name "unconnected-(U1-PB14-Pad36)") (class "Default")
      (node (ref "U1") (pin "36") (pinfunction "PB14_36") (pintype "bidirectional"))
    )
    (net (code "63") (name "unconnected-(U1-PB15-Pad37)") (class "Default")
      (node (ref "U1") (pin "37") (pinfunction "PB15_37") (pintype "bidirectional"))
    )
    (net (code "64") (name "unconnected-(U1-PC3-Pad11)") (class "Default")
      (node (ref "U1") (pin "11") (pinfunction "PC3_11") (pintype "bidirectional"))
    )
    (net (code "65") (name "unconnected-(U1-PC7-Pad39)") (class "Default")
      (node (ref "U1") (pin "39") (pinfunction "PC7_39") (pintype "bidirectional"))
    )
    (net (code "66") (name "unconnected-(U1-PC8-Pad40)") (class "Default")
      (node (ref "U1") (pin "40") (pinfunction "PC8_40") (pintype "bidirectional"))
    )
    (net (code "67") (name "unconnected-(U1-PC9-Pad41)") (class "Default")
      (node (ref "U1") (pin "41") (pinfunction "PC9_41") (pintype "bidirectional"))
    )
    (net (code "68") (name "unconnected-(U1-PC10-Pad52)") (class "Default")
      (node (ref "U1") (pin "52") (pinfunction "PC10_52") (pintype "bidirectional"))
    )
    (net (code "69") (name "unconnected-(U1-PC11-Pad53)") (class "Default")
      (node (ref "U1") (pin "53") (pinfunction "PC11_53") (pintype "bidirectional"))
    )
    (net (code "70") (name "unconnected-(U1-PC12-Pad54)") (class "Default")
      (node (ref "U1") (pin "54") (pinfunction "PC12_54") (pintype "bidirectional"))
    )
    (net (code "71") (name "unconnected-(U1-PC13-Pad2)") (class "Default")
      (node (ref "U1") (pin "2") (pinfunction "PC13_2") (pintype "bidirectional"))
    )
    (net (code "72") (name "unconnected-(U1-PC14-OSC32_IN-Pad3)") (class "Default")
      (node (ref "U1") (pin "3") (pinfunction "PC14-OSC32_IN_3") (pintype "bidirectional"))
    )
    (net (code "73") (name "unconnected-(U1-PC15-OSC32_OUT-Pad4)") (class "Default")
      (node (ref "U1") (pin "4") (pinfunction "PC15-OSC32_OUT_4") (pintype "bidirectional"))
    )
    (net (code "74") (name "unconnected-(U1-PD2-Pad55)") (class "Default")
      (node (ref "U1") (pin "55") (pinfunction "PD2_55") (pintype "bidirectional"))
    )
    (net (code "75") (name "unconnected-(U1-PF0-OSC_IN-Pad5)") (class "Default")
      (node (ref "U1") (pin "5") (pinfunction "PF0-OSC_IN_5") (pintype "input"))
    )
    (net (code "76") (name "unconnected-(U1-PF1-OSC_OUT-Pad6)") (class "Default")
      (node (ref "U1") (pin "6") (pinfunction "PF1-OSC_OUT_6") (pintype "bidirectional"))
    )
  )
)
